# V03.net
KiCad netlist of a schematic drawn in Altium Designer
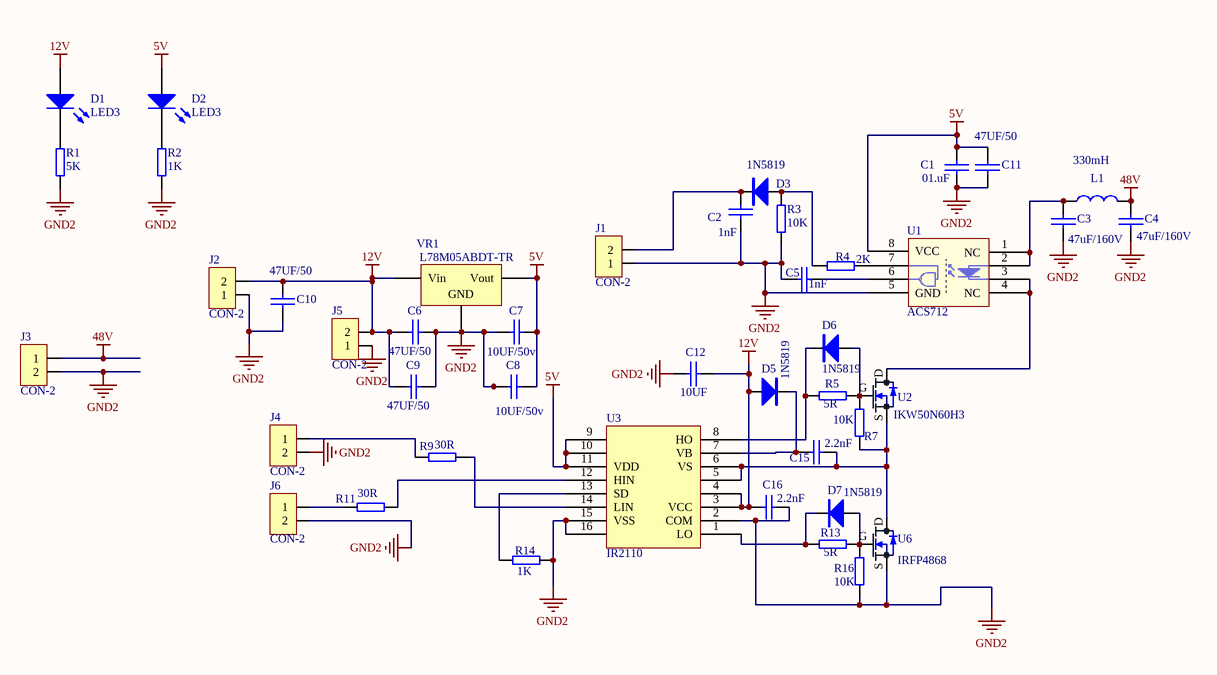
[diagram p0: 发送端V03.SchDoc]

(export (version "E")
  (design (tool "Eeschema 10.0.6"))
  (components
    (comp (ref "C1") (value "01.uF") (footprint "1206_C") (libsource (lib "WegeV1") (part "CAP")))
    (comp (ref "C2") (value "1nF") (footprint "1206_C") (libsource (lib "WegeV1") (part "CAP")))
    (comp (ref "C3") (value "47uF/160V") (footprint "C3618") (libsource (lib "WegeV1") (part "CAP")))
    (comp (ref "C4") (value "47uF/160V") (footprint "C3618") (libsource (lib "WegeV1") (part "CAP")))
    (comp (ref "C5") (value "1nF") (footprint "1206_C") (libsource (lib "WegeV1") (part "CAP")))
    (comp (ref "C6") (value "47UF/50") (footprint "1206_C") (libsource (lib "WegeV1") (part "CAP")))
    (comp (ref "C7") (value "10UF/50v") (footprint "1206_C") (libsource (lib "WegeV1") (part "CAP")))
    (comp (ref "C8") (value "10UF/50v") (footprint "1206_C") (libsource (lib "WegeV1") (part "CAP")))
    (comp (ref "C9") (value "47UF/50") (footprint "1206_C") (libsource (lib "WegeV1") (part "CAP")))
    (comp (ref "C10") (value "47UF/50") (footprint "C1020") (libsource (lib "WegeV1") (part "CAP")))
    (comp (ref "C11") (value "47UF/50") (footprint "C1020") (libsource (lib "WegeV1") (part "CAP")))
    (comp (ref "C12") (value "10UF") (footprint "1206_C") (libsource (lib "WegeV1") (part "CAP")))
    (comp (ref "C15") (value "2.2nF") (footprint "1206_C") (libsource (lib "WegeV1") (part "CAP")))
    (comp (ref "C16") (value "2.2nF") (footprint "1206_C") (libsource (lib "WegeV1") (part "CAP")))
    (comp (ref "D1")
      (value "LED3")
      (footprint "1206_R")
      (description "Typical BLUE SiC LED")
      (fields (field (name "PUBLISHER") "Altium Limited"))
      (libsource (lib "Miscellaneous Devices") (part "LED3"))
    )
    (comp (ref "D2")
      (value "LED3")
      (footprint "1206_R")
      (description "Typical BLUE SiC LED")
      (fields (field (name "PUBLISHER") "Altium Limited"))
      (libsource (lib "Miscellaneous Devices") (part "LED3"))
    )
    (comp (ref "D3")
      (value "1N5819")
      (footprint "1206_R")
      (description "1N4148WS IN4148 0805 SOD323 丝印T4 贴片开关二极管")
      (libsource (lib "WegeV1") (part "1N4148"))
    )
    (comp (ref "D5")
      (value "1N5819")
      (footprint "1206_R")
      (description "1N4148WS IN4148 0805 SOD323 丝印T4 贴片开关二极管")
      (libsource (lib "WegeV1") (part "1N4148"))
    )
    (comp (ref "D6")
      (value "1N5819")
      (footprint "1206_R")
      (description "1N4148WS IN4148 0805 SOD323 丝印T4 贴片开关二极管")
      (libsource (lib "WegeV1") (part "1N4148"))
    )
    (comp (ref "D7")
      (value "1N5819")
      (footprint "1206_R")
      (description "1N4148WS IN4148 0805 SOD323 丝印T4 贴片开关二极管")
      (libsource (lib "WegeV1") (part "1N4148"))
    )
    (comp (ref "J1") (value "CON-2") (footprint "HDR1X2") (libsource (lib "") (part "CON-2_1")))
    (comp (ref "J2") (value "CON-2") (footprint "HDR1X2") (libsource (lib "") (part "CON-2_1")))
    (comp (ref "J3") (value "CON-2") (footprint "F396P2-1") (libsource (lib "WegeV1") (part "CON-2")))
    (comp (ref "J4") (value "CON-2") (footprint "GPSPIN") (libsource (lib "WegeV1") (part "CON-2")))
    (comp (ref "J5") (value "CON-2") (footprint "F396P2-1") (libsource (lib "") (part "CON-2_1")))
    (comp (ref "J6") (value "CON-2") (footprint "GPSPIN") (libsource (lib "WegeV1") (part "CON-2")))
    (comp (ref "L1")
      (value "330mH")
      (footprint "H3.3")
      (description "CD75--2.2mH 222M 贴片功率电感绕线功率电感 7*7.8*5mm")
      (libsource (lib "WegeV1") (part "INL"))
    )
    (comp (ref "R1") (value "5K") (footprint "1206_R") (libsource (lib "WegeV1") (part "RES")))
    (comp (ref "R2") (value "1K") (footprint "1206_R") (libsource (lib "WegeV1") (part "RES")))
    (comp (ref "R3") (value "10K") (footprint "1206_R") (libsource (lib "WegeV1") (part "RES")))
    (comp (ref "R4") (value "2K") (footprint "1206_R") (libsource (lib "WegeV1") (part "RES")))
    (comp (ref "R5") (value "5R") (footprint "1206_R") (libsource (lib "WegeV1") (part "RES")))
    (comp (ref "R7") (value "10K") (footprint "1206_R") (libsource (lib "WegeV1") (part "RES")))
    (comp (ref "R9") (value "30R") (footprint "1206_R") (libsource (lib "WegeV1") (part "RES")))
    (comp (ref "R11") (value "30R") (footprint "1206_R") (libsource (lib "WegeV1") (part "RES")))
    (comp (ref "R13") (value "5R") (footprint "1206_R") (libsource (lib "WegeV1") (part "RES")))
    (comp (ref "R14") (value "1K") (footprint "1206_R") (libsource (lib "WegeV1") (part "RES")))
    (comp (ref "R16") (value "10K") (footprint "1206_R") (libsource (lib "WegeV1") (part "RES")))
    (comp (ref "U1")
      (value "ACS712")
      (footprint "SOIC-8_150mil")
      (description "贴片光耦")
      (libsource (lib "Miscellaneous Devices LC") (part "6N137S(TA)_[C16496]"))
    )
    (comp (ref "U2") (value "IKW50N60H3") (footprint "TO-274") (libsource (lib "WegeV1") (part "NMOS")))
    (comp (ref "U3")
      (value "IR2110")
      (footprint "SOIC-16_300mil")
      (libsource (lib "IC_temp") (part "IR2110"))
    )
    (comp (ref "U6") (value "IRFP4868") (footprint "TO-274") (libsource (lib "WegeV1") (part "NMOS")))
    (comp (ref "VR1")
      (value "L78M05ABDT-TR")
      (footprint "TO-220")
      (description "低压差线性稳压(LDO)")
      (libsource (lib "Miscellaneous Devices LC") (part "TO-252-2 L78M05ABDT-TR"))
    )
  )
  (nets
    (net (code "1") (name "5V") (class "Default")
      (node (ref "C1") (pin "1") (pinfunction "1_1") (pintype "passive"))
      (node (ref "C11") (pin "1") (pinfunction "1_1") (pintype "passive"))
      (node (ref "C7") (pin "1") (pinfunction "1_1") (pintype "passive"))
      (node (ref "C8") (pin "1") (pinfunction "1_1") (pintype "passive"))
      (node (ref "D2") (pin "1") (pinfunction "A_1") (pintype "passive"))
      (node (ref "U1") (pin "8") (pinfunction "VCC_8") (pintype "passive"))
      (node (ref "U3") (pin "10") (pintype "passive"))
      (node (ref "U3") (pin "11") (pinfunction "VDD_11") (pintype "passive"))
      (node (ref "U3") (pin "9") (pintype "passive"))
      (node (ref "VR1") (pin "S") (pinfunction "Vout_S") (pintype "passive"))
    )
    (net (code "2") (name "12V") (class "Default")
      (node (ref "C10") (pin "1") (pinfunction "1_1") (pintype "passive"))
      (node (ref "C12") (pin "1") (pinfunction "1_1") (pintype "passive"))
      (node (ref "C16") (pin "2") (pinfunction "2_2") (pintype "passive"))
      (node (ref "C6") (pin "2") (pinfunction "2_2") (pintype "passive"))
      (node (ref "C9") (pin "2") (pinfunction "2_2") (pintype "passive"))
      (node (ref "D1") (pin "1") (pinfunction "A_1") (pintype "passive"))
      (node (ref "D5") (pin "1") (pinfunction "A_1") (pintype "passive"))
      (node (ref "J2") (pin "2") (pinfunction "2_2") (pintype "passive"))
      (node (ref "J5") (pin "2") (pinfunction "2_2") (pintype "passive"))
      (node (ref "U3") (pin "3") (pinfunction "VCC_3") (pintype "passive"))
      (node (ref "U3") (pin "4") (pintype "passive"))
      (node (ref "VR1") (pin "G") (pinfunction "Vin_G") (pintype "passive"))
    )
    (net (code "3") (name "48V") (class "Default")
      (node (ref "C4") (pin "1") (pinfunction "1_1") (pintype "passive"))
      (node (ref "J3") (pin "1") (pinfunction "1_1") (pintype "passive"))
      (node (ref "L1") (pin "1") (pinfunction "1_1") (pintype "passive"))
    )
    (net (code "4") (name "GND2") (class "Default")
      (node (ref "C1") (pin "2") (pinfunction "2_2") (pintype "passive"))
      (node (ref "C10") (pin "2") (pinfunction "2_2") (pintype "passive"))
      (node (ref "C11") (pin "2") (pinfunction "2_2") (pintype "passive"))
      (node (ref "C12") (pin "2") (pinfunction "2_2") (pintype "passive"))
      (node (ref "C16") (pin "1") (pinfunction "1_1") (pintype "passive"))
      (node (ref "C2") (pin "2") (pinfunction "2_2") (pintype "passive"))
      (node (ref "C3") (pin "2") (pinfunction "2_2") (pintype "passive"))
      (node (ref "C4") (pin "2") (pinfunction "2_2") (pintype "passive"))
      (node (ref "C5") (pin "2") (pinfunction "2_2") (pintype "passive"))
      (node (ref "C6") (pin "1") (pinfunction "1_1") (pintype "passive"))
      (node (ref "C7") (pin "2") (pinfunction "2_2") (pintype "passive"))
      (node (ref "C8") (pin "2") (pinfunction "2_2") (pintype "passive"))
      (node (ref "C9") (pin "1") (pinfunction "1_1") (pintype "passive"))
      (node (ref "J1") (pin "1") (pinfunction "1_1") (pintype "passive"))
      (node (ref "J2") (pin "1") (pinfunction "1_1") (pintype "passive"))
      (node (ref "J3") (pin "2") (pinfunction "2_2") (pintype "passive"))
      (node (ref "J4") (pin "2") (pinfunction "2_2") (pintype "passive"))
      (node (ref "J5") (pin "1") (pinfunction "1_1") (pintype "passive"))
      (node (ref "J6") (pin "2") (pinfunction "2_2") (pintype "passive"))
      (node (ref "R1") (pin "1") (pinfunction "1_1") (pintype "passive"))
      (node (ref "R14") (pin "2") (pinfunction "2_2") (pintype "passive"))
      (node (ref "R16") (pin "1") (pinfunction "1_1") (pintype "passive"))
      (node (ref "R2") (pin "1") (pinfunction "1_1") (pintype "passive"))
      (node (ref "R3") (pin "2") (pinfunction "2_2") (pintype "passive"))
      (node (ref "U1") (pin "5") (pinfunction "GND_5") (pintype "passive"))
      (node (ref "U3") (pin "15") (pinfunction "VSS_15") (pintype "passive"))
      (node (ref "U3") (pin "16") (pintype "passive"))
      (node (ref "U3") (pin "2") (pinfunction "COM_2") (pintype "passive"))
      (node (ref "U6") (pin "S") (pinfunction "S_S") (pintype "passive"))
      (node (ref "VR1") (pin "D") (pinfunction "GND_D") (pintype "passive"))
    )
    (net (code "5") (name "Net-(D1-K)") (class "Default")
      (node (ref "D1") (pin "2") (pinfunction "K_2") (pintype "passive"))
      (node (ref "R1") (pin "2") (pinfunction "2_2") (pintype "passive"))
    )
    (net (code "6") (name "Net-(D2-K)") (class "Default")
      (node (ref "D2") (pin "2") (pinfunction "K_2") (pintype "passive"))
      (node (ref "R2") (pin "2") (pinfunction "2_2") (pintype "passive"))
    )
    (net (code "7") (name "Net-(D3-A)") (class "Default")
      (node (ref "D3") (pin "1") (pinfunction "A_1") (pintype "passive"))
      (node (ref "R3") (pin "1") (pinfunction "1_1") (pintype "passive"))
      (node (ref "R4") (pin "2") (pinfunction "2_2") (pintype "passive"))
    )
    (net (code "8") (name "Net-(D3-K)") (class "Default")
      (node (ref "C2") (pin "1") (pinfunction "1_1") (pintype "passive"))
      (node (ref "D3") (pin "2") (pinfunction "K_2") (pintype "passive"))
      (node (ref "J1") (pin "2") (pinfunction "2_2") (pintype "passive"))
    )
    (net (code "9") (name "Net-(D5-K)") (class "Default")
      (node (ref "C15") (pin "2") (pinfunction "2_2") (pintype "passive"))
      (node (ref "D5") (pin "2") (pinfunction "K_2") (pintype "passive"))
      (node (ref "U3") (pin "7") (pinfunction "VB_7") (pintype "passive"))
    )
    (net (code "10") (name "Net-(D6-A)") (class "Default")
      (node (ref "D6") (pin "1") (pinfunction "A_1") (pintype "passive"))
      (node (ref "R5") (pin "2") (pinfunction "2_2") (pintype "passive"))
      (node (ref "R7") (pin "2") (pinfunction "2_2") (pintype "passive"))
      (node (ref "U2") (pin "G") (pinfunction "G_G") (pintype "passive"))
    )
    (net (code "11") (name "Net-(D6-K)") (class "Default")
      (node (ref "D6") (pin "2") (pinfunction "K_2") (pintype "passive"))
      (node (ref "R5") (pin "1") (pinfunction "1_1") (pintype "passive"))
      (node (ref "U3") (pin "8") (pinfunction "HO_8") (pintype "passive"))
    )
    (net (code "12") (name "Net-(D7-A)") (class "Default")
      (node (ref "D7") (pin "1") (pinfunction "A_1") (pintype "passive"))
      (node (ref "R13") (pin "2") (pinfunction "2_2") (pintype "passive"))
      (node (ref "R16") (pin "2") (pinfunction "2_2") (pintype "passive"))
      (node (ref "U6") (pin "G") (pinfunction "G_G") (pintype "passive"))
    )
    (net (code "13") (name "Net-(D7-K)") (class "Default")
      (node (ref "D7") (pin "2") (pinfunction "K_2") (pintype "passive"))
      (node (ref "R13") (pin "1") (pinfunction "1_1") (pintype "passive"))
      (node (ref "U3") (pin "1") (pinfunction "LO_1") (pintype "passive"))
    )
    (net (code "14") (name "Net-(J4-Pad1)") (class "Default")
      (node (ref "J4") (pin "1") (pinfunction "1_1") (pintype "passive"))
      (node (ref "R9") (pin "1") (pinfunction "1_1") (pintype "passive"))
    )
    (net (code "15") (name "Net-(J6-Pad1)") (class "Default")
      (node (ref "J6") (pin "1") (pinfunction "1_1") (pintype "passive"))
      (node (ref "R11") (pin "1") (pinfunction "1_1") (pintype "passive"))
    )
    (net (code "16") (name "Net-(U1-A)") (class "Default")
      (node (ref "C3") (pin "1") (pinfunction "1_1") (pintype "passive"))
      (node (ref "L1") (pin "2") (pinfunction "2_2") (pintype "passive"))
      (node (ref "U1") (pin "1") (pinfunction "NC_1") (pintype "passive"))
      (node (ref "U1") (pin "2") (pinfunction "A_2") (pintype "passive"))
    )
    (net (code "17") (name "Net-(U1-K)") (class "Default")
      (node (ref "U1") (pin "3") (pinfunction "K_3") (pintype "passive"))
      (node (ref "U1") (pin "4") (pinfunction "NC_4") (pintype "passive"))
      (node (ref "U2") (pin "D") (pinfunction "D_D") (pintype "passive"))
    )
    (net (code "18") (name "Net-(U1-VE)") (class "Default")
      (node (ref "R4") (pin "1") (pinfunction "1_1") (pintype "passive"))
      (node (ref "U1") (pin "7") (pinfunction "VE_7") (pintype "passive"))
    )
    (net (code "19") (name "Net-(U1-VO)") (class "Default")
      (node (ref "C5") (pin "1") (pinfunction "1_1") (pintype "passive"))
      (node (ref "U1") (pin "6") (pinfunction "VO_6") (pintype "passive"))
    )
    (net (code "20") (name "Net-(U3-HIN)") (class "Default")
      (node (ref "R11") (pin "2") (pinfunction "2_2") (pintype "passive"))
      (node (ref "U3") (pin "12") (pinfunction "HIN_12") (pintype "passive"))
    )
    (net (code "21") (name "Net-(U3-LIN)") (class "Default")
      (node (ref "R9") (pin "2") (pinfunction "2_2") (pintype "passive"))
      (node (ref "U3") (pin "14") (pinfunction "LIN_14") (pintype "passive"))
    )
    (net (code "22") (name "Net-(U3-SD)") (class "Default")
      (node (ref "R14") (pin "1") (pinfunction "1_1") (pintype "passive"))
      (node (ref "U3") (pin "13") (pinfunction "SD_13") (pintype "passive"))
    )
    (net (code "23") (name "Net-(U3-VS)") (class "Default")
      (node (ref "C15") (pin "1") (pinfunction "1_1") (pintype "passive"))
      (node (ref "R7") (pin "1") (pinfunction "1_1") (pintype "passive"))
      (node (ref "U2") (pin "S") (pinfunction "S_S") (pintype "passive"))
      (node (ref "U3") (pin "5") (pintype "passive"))
      (node (ref "U3") (pin "6") (pinfunction "VS_6") (pintype "passive"))
      (node (ref "U6") (pin "D") (pinfunction "D_D") (pintype "passive"))
    )
  )
)
